# SHALightSwitch.net
KiCad netlist of a schematic drawn in EAGLE
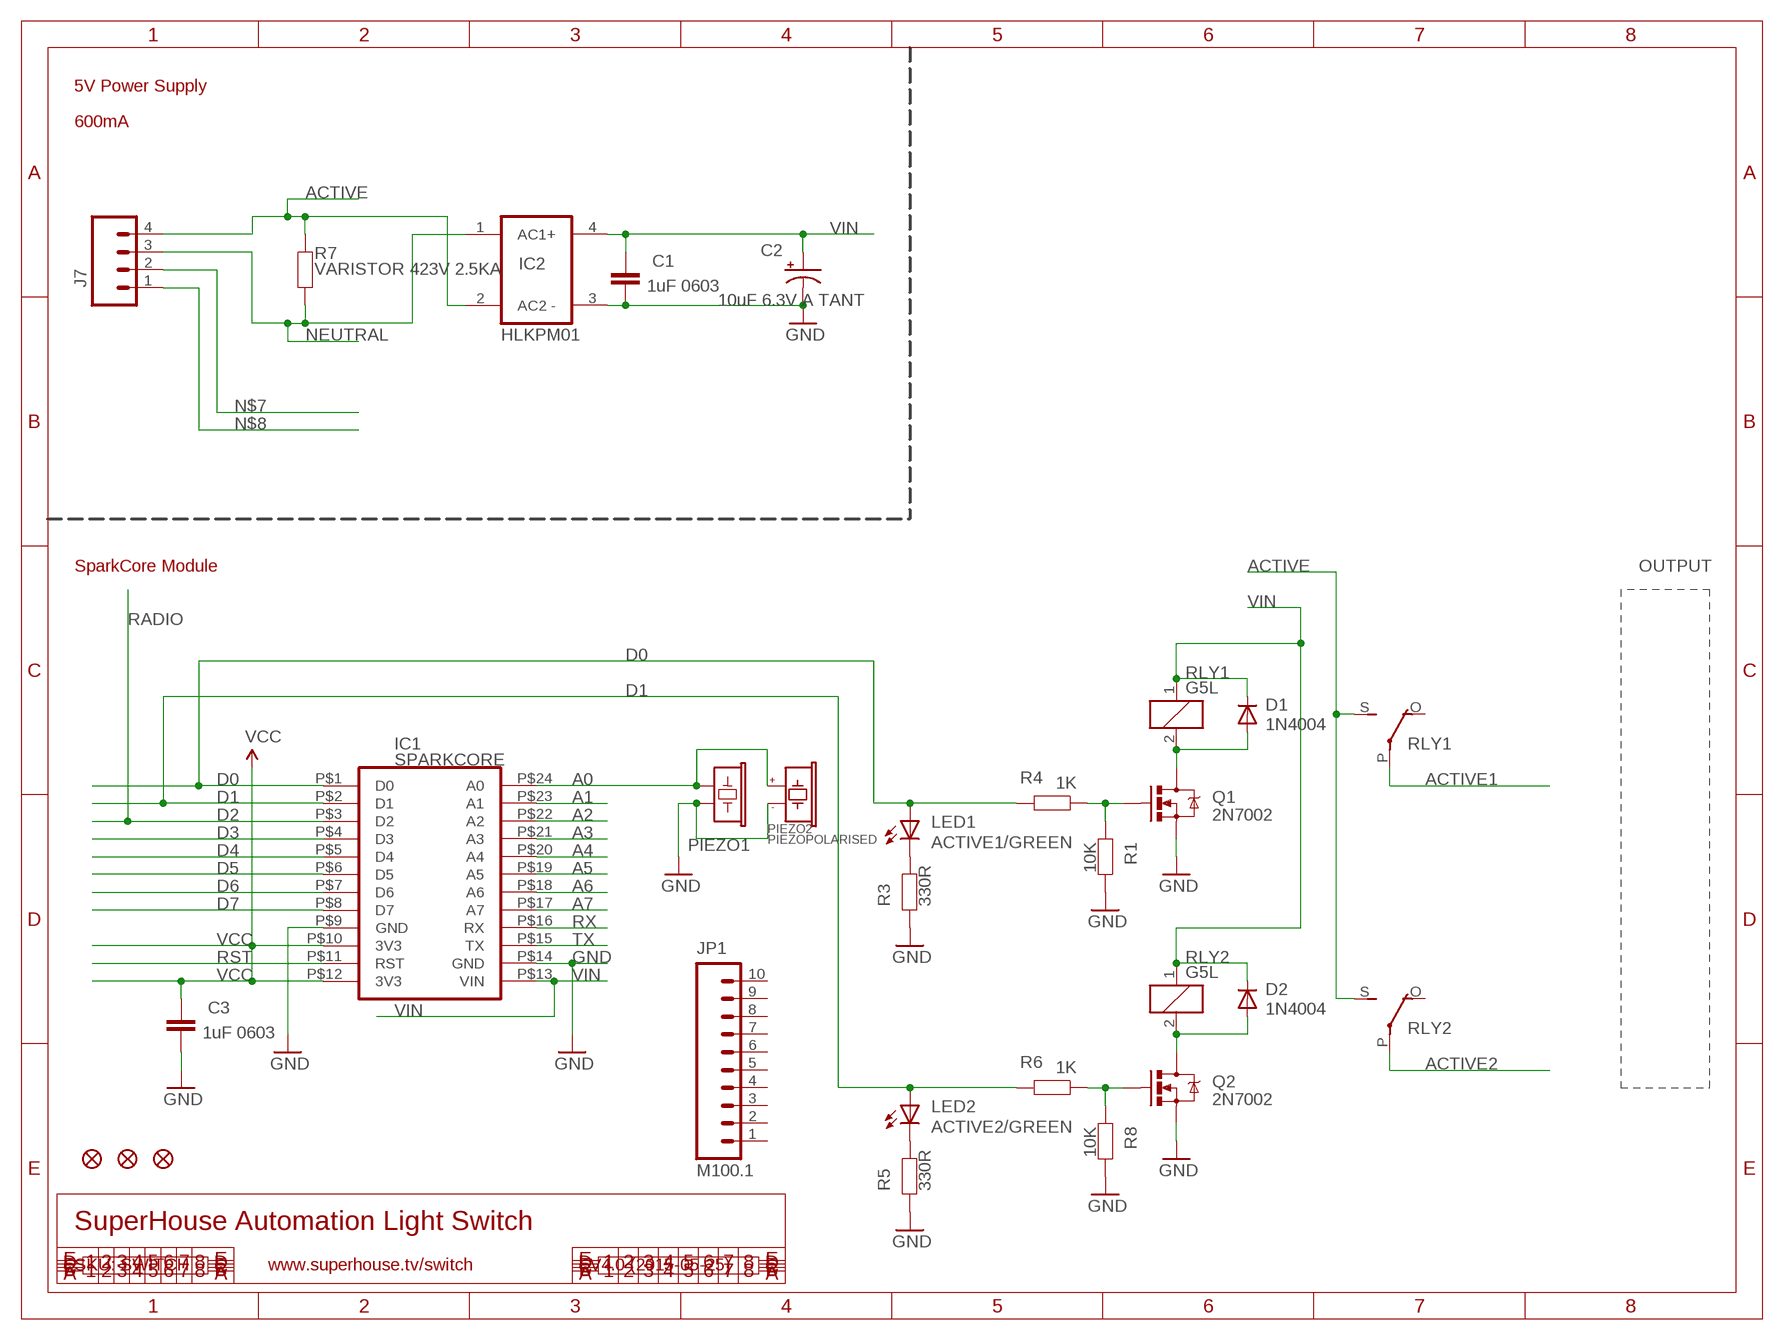
[diagram p0: schematic, sheet 1]

(export (version "E")
  (design (tool "Eeschema 10.0.6"))
  (components
    (comp (ref "C1")
      (value "1uF 0603")
      (footprint "eagle-import:0603@1")
      (libsource (lib "eagle-import") (part "CAP0603"))
    )
    (comp (ref "C2")
      (value "10uF 6.3V A TANT")
      (footprint "eagle-import:EIA3216")
      (libsource (lib "eagle-import") (part "CAP_POL1206"))
    )
    (comp (ref "C3")
      (value "1uF 0603")
      (footprint "eagle-import:0603@1")
      (libsource (lib "eagle-import") (part "CAP0603"))
    )
    (comp (ref "D1")
      (value "1N4004")
      (footprint "eagle-import:SMB-DIODE")
      (libsource (lib "eagle-import") (part "DIODESMB"))
    )
    (comp (ref "D2")
      (value "1N4004")
      (footprint "eagle-import:SMB-DIODE")
      (libsource (lib "eagle-import") (part "DIODESMB"))
    )
    (comp (ref "FID1")
      (value "FIDUCIAL1X2.5")
      (footprint "eagle-import:FIDUCIAL-1X2.5")
      (libsource (lib "eagle-import") (part "FIDUCIAL1X2.5"))
    )
    (comp (ref "FID2")
      (value "FIDUCIAL1X2.5")
      (footprint "eagle-import:FIDUCIAL-1X2.5")
      (libsource (lib "eagle-import") (part "FIDUCIAL1X2.5"))
    )
    (comp (ref "FID3")
      (value "FIDUCIAL1X2.5")
      (footprint "eagle-import:FIDUCIAL-1X2.5")
      (libsource (lib "eagle-import") (part "FIDUCIAL1X2.5"))
    )
    (comp (ref "IC1")
      (value "SPARKCORE")
      (footprint "eagle-import:SPARKCORE")
      (libsource (lib "eagle-import") (part "SPARKCORE"))
    )
    (comp (ref "IC2")
      (value "HLKPM01")
      (footprint "eagle-import:HLKPM01")
      (libsource (lib "eagle-import") (part "HLKPM01"))
    )
    (comp (ref "J7")
      (value "M04SCREW")
      (footprint "eagle-import:SCREWTERMINAL-3.5MM-4")
      (libsource (lib "eagle-import") (part "M04SCREW"))
    )
    (comp (ref "JP1")
      (value "M100.1")
      (footprint "eagle-import:1X10")
      (libsource (lib "eagle-import") (part "M100.1"))
    )
    (comp (ref "LED1")
      (value "ACTIVE1/GREEN")
      (footprint "eagle-import:LED-0603")
      (libsource (lib "eagle-import") (part "LED0603"))
    )
    (comp (ref "LED2")
      (value "ACTIVE2/GREEN")
      (footprint "eagle-import:LED-0603")
      (libsource (lib "eagle-import") (part "LED0603"))
    )
    (comp (ref "PIEZO1")
      (value "BUZZERSMD12X12")
      (footprint "eagle-import:BUZZER-12X12-SMT")
      (libsource (lib "eagle-import") (part "BUZZERSMD12X12"))
    )
    (comp (ref "PIEZO2")
      (value "PIEZOPOLARISED")
      (footprint "eagle-import:PIEZO12MMWIDEPOLARISED")
      (libsource (lib "eagle-import") (part "PIEZOPOLARISED"))
    )
    (comp (ref "Q1")
      (value "2N7002")
      (footprint "eagle-import:SOT23-3")
      (libsource (lib "eagle-import") (part "MOSFET-NCHANNELSMD"))
    )
    (comp (ref "Q2")
      (value "2N7002")
      (footprint "eagle-import:SOT23-3")
      (libsource (lib "eagle-import") (part "MOSFET-NCHANNELSMD"))
    )
    (comp (ref "R1")
      (value "10K")
      (footprint "eagle-import:0603")
      (libsource (lib "eagle-import") (part "RESISTOR0603"))
    )
    (comp (ref "R3")
      (value "330R")
      (footprint "eagle-import:0603")
      (libsource (lib "eagle-import") (part "RESISTOR0603"))
    )
    (comp (ref "R4")
      (value "1K")
      (footprint "eagle-import:0603")
      (libsource (lib "eagle-import") (part "RESISTOR0603"))
    )
    (comp (ref "R5")
      (value "330R")
      (footprint "eagle-import:0603")
      (libsource (lib "eagle-import") (part "RESISTOR0603"))
    )
    (comp (ref "R6")
      (value "1K")
      (footprint "eagle-import:0603")
      (libsource (lib "eagle-import") (part "RESISTOR0603"))
    )
    (comp (ref "R7")
      (value "VARISTOR 423V 2.5KA")
      (footprint "eagle-import:AXIAL-0.3")
      (libsource (lib "eagle-import") (part "freetronics-master-v1.1_RESISTORPTH1"))
    )
    (comp (ref "R8")
      (value "10K")
      (footprint "eagle-import:0603")
      (libsource (lib "eagle-import") (part "RESISTOR0603"))
    )
    (comp (ref "RLY1")
      (value "G5L")
      (footprint "eagle-import:G5LE")
      (libsource (lib "eagle-import") (part "G5L"))
    )
    (comp (ref "RLY2")
      (value "G5L")
      (footprint "eagle-import:G5LE")
      (libsource (lib "eagle-import") (part "G5L"))
    )
  )
  (nets
    (net (code "1") (name "/A0") (class "Default")
      (node (ref "IC1") (pin "P$24") (pinfunction "A0_P$24") (pintype "bidirectional"))
      (node (ref "PIEZO1") (pin "1") (pinfunction "1_1") (pintype "passive"))
      (node (ref "PIEZO2") (pin "1") (pinfunction "+_1") (pintype "bidirectional"))
    )
    (net (code "2") (name "/A1") (class "Default")
      (node (ref "IC1") (pin "P$23") (pinfunction "A1_P$23") (pintype "bidirectional"))
    )
    (net (code "3") (name "/A2") (class "Default")
      (node (ref "IC1") (pin "P$22") (pinfunction "A2_P$22") (pintype "bidirectional"))
    )
    (net (code "4") (name "/A3") (class "Default")
      (node (ref "IC1") (pin "P$21") (pinfunction "A3_P$21") (pintype "bidirectional"))
    )
    (net (code "5") (name "/A4") (class "Default")
      (node (ref "IC1") (pin "P$20") (pinfunction "A4_P$20") (pintype "bidirectional"))
    )
    (net (code "6") (name "/A5") (class "Default")
      (node (ref "IC1") (pin "P$19") (pinfunction "A5_P$19") (pintype "bidirectional"))
    )
    (net (code "7") (name "/A6") (class "Default")
      (node (ref "IC1") (pin "P$18") (pinfunction "A6_P$18") (pintype "bidirectional"))
    )
    (net (code "8") (name "/A7") (class "Default")
      (node (ref "IC1") (pin "P$17") (pinfunction "A7_P$17") (pintype "bidirectional"))
    )
    (net (code "9") (name "/ACTIVE") (class "Default")
      (node (ref "IC2") (pin "2") (pinfunction "AC2_2") (pintype "bidirectional"))
      (node (ref "J7") (pin "4") (pinfunction "4_4") (pintype "passive"))
      (node (ref "R7") (pin "P$2") (pinfunction "2_P$2") (pintype "passive"))
      (node (ref "RLY1") (pin "S") (pinfunction "S_S") (pintype "passive"))
      (node (ref "RLY2") (pin "S") (pinfunction "S_S") (pintype "passive"))
    )
    (net (code "10") (name "/ACTIVE1") (class "Default")
      (node (ref "RLY1") (pin "P") (pinfunction "P_P") (pintype "passive"))
    )
    (net (code "11") (name "/ACTIVE2") (class "Default")
      (node (ref "RLY2") (pin "P") (pinfunction "P_P") (pintype "passive"))
    )
    (net (code "12") (name "/D0") (class "Default")
      (node (ref "IC1") (pin "P$1") (pinfunction "D0_P$1") (pintype "bidirectional"))
      (node (ref "LED1") (pin "A") (pinfunction "A_A") (pintype "passive"))
      (node (ref "R4") (pin "2") (pinfunction "2_2") (pintype "passive"))
    )
    (net (code "13") (name "/D1") (class "Default")
      (node (ref "IC1") (pin "P$2") (pinfunction "D1_P$2") (pintype "bidirectional"))
      (node (ref "LED2") (pin "A") (pinfunction "A_A") (pintype "passive"))
      (node (ref "R6") (pin "2") (pinfunction "2_2") (pintype "passive"))
    )
    (net (code "14") (name "/D2") (class "Default")
      (node (ref "IC1") (pin "P$3") (pinfunction "D2_P$3") (pintype "bidirectional"))
    )
    (net (code "15") (name "/D3") (class "Default")
      (node (ref "IC1") (pin "P$4") (pinfunction "D3_P$4") (pintype "bidirectional"))
    )
    (net (code "16") (name "/D4") (class "Default")
      (node (ref "IC1") (pin "P$5") (pinfunction "D4_P$5") (pintype "bidirectional"))
    )
    (net (code "17") (name "/D5") (class "Default")
      (node (ref "IC1") (pin "P$6") (pinfunction "D5_P$6") (pintype "bidirectional"))
    )
    (net (code "18") (name "/D6") (class "Default")
      (node (ref "IC1") (pin "P$7") (pinfunction "D6_P$7") (pintype "bidirectional"))
    )
    (net (code "19") (name "/D7") (class "Default")
      (node (ref "IC1") (pin "P$8") (pinfunction "D7_P$8") (pintype "bidirectional"))
    )
    (net (code "20") (name "/N$7") (class "Default")
      (node (ref "J7") (pin "2") (pinfunction "2_2") (pintype "passive"))
    )
    (net (code "21") (name "/N$8") (class "Default")
      (node (ref "J7") (pin "1") (pinfunction "1_1") (pintype "passive"))
    )
    (net (code "22") (name "/NEUTRAL") (class "Default")
      (node (ref "IC2") (pin "1") (pinfunction "AC1_1") (pintype "bidirectional"))
      (node (ref "J7") (pin "3") (pinfunction "3_3") (pintype "passive"))
      (node (ref "R7") (pin "P$1") (pinfunction "1_P$1") (pintype "passive"))
    )
    (net (code "23") (name "/RST") (class "Default")
      (node (ref "IC1") (pin "P$11") (pinfunction "RST_P$11") (pintype "bidirectional"))
    )
    (net (code "24") (name "/RX") (class "Default")
      (node (ref "IC1") (pin "P$16") (pinfunction "RX_P$16") (pintype "bidirectional"))
    )
    (net (code "25") (name "/TX") (class "Default")
      (node (ref "IC1") (pin "P$15") (pinfunction "TX_P$15") (pintype "bidirectional"))
    )
    (net (code "26") (name "/VIN") (class "Default")
      (node (ref "C1") (pin "1") (pinfunction "1_1") (pintype "passive"))
      (node (ref "C2") (pin "A") (pinfunction "+_A") (pintype "passive"))
      (node (ref "D1") (pin "C") (pinfunction "C_C") (pintype "passive"))
      (node (ref "D2") (pin "C") (pinfunction "C_C") (pintype "passive"))
      (node (ref "IC1") (pin "P$13") (pinfunction "VIN_P$13") (pintype "bidirectional"))
      (node (ref "IC2") (pin "4") (pinfunction "+_4") (pintype "bidirectional"))
      (node (ref "RLY1") (pin "1") (pinfunction "1_1") (pintype "passive"))
      (node (ref "RLY2") (pin "1") (pinfunction "1_1") (pintype "passive"))
    )
    (net (code "27") (name "GND") (class "Default")
      (node (ref "C1") (pin "2") (pinfunction "2_2") (pintype "passive"))
      (node (ref "C2") (pin "C") (pinfunction "-_C") (pintype "passive"))
      (node (ref "C3") (pin "2") (pinfunction "2_2") (pintype "passive"))
      (node (ref "IC1") (pin "P$14") (pinfunction "GND_P$14") (pintype "bidirectional"))
      (node (ref "IC1") (pin "P$9") (pinfunction "GND_P$9") (pintype "bidirectional"))
      (node (ref "IC2") (pin "3") (pinfunction "-_3") (pintype "bidirectional"))
      (node (ref "PIEZO1") (pin "2") (pinfunction "2_2") (pintype "passive"))
      (node (ref "PIEZO2") (pin "2") (pinfunction "-_2") (pintype "bidirectional"))
      (node (ref "Q1") (pin "2") (pinfunction "S_2") (pintype "passive"))
      (node (ref "Q2") (pin "2") (pinfunction "S_2") (pintype "passive"))
      (node (ref "R1") (pin "2") (pinfunction "2_2") (pintype "passive"))
      (node (ref "R3") (pin "1") (pinfunction "1_1") (pintype "passive"))
      (node (ref "R5") (pin "1") (pinfunction "1_1") (pintype "passive"))
      (node (ref "R8") (pin "2") (pinfunction "2_2") (pintype "passive"))
    )
    (net (code "28") (name "Net-(LED1-PadC)") (class "Default")
      (node (ref "LED1") (pin "C") (pinfunction "C_C") (pintype "passive"))
      (node (ref "R3") (pin "2") (pinfunction "2_2") (pintype "passive"))
    )
    (net (code "29") (name "Net-(LED2-PadC)") (class "Default")
      (node (ref "LED2") (pin "C") (pinfunction "C_C") (pintype "passive"))
      (node (ref "R5") (pin "2") (pinfunction "2_2") (pintype "passive"))
    )
    (net (code "30") (name "Net-(Q1-D)") (class "Default")
      (node (ref "D1") (pin "A") (pinfunction "A_A") (pintype "passive"))
      (node (ref "Q1") (pin "3") (pinfunction "D_3") (pintype "passive"))
      (node (ref "RLY1") (pin "2") (pinfunction "2_2") (pintype "passive"))
    )
    (net (code "31") (name "Net-(Q1-G)") (class "Default")
      (node (ref "Q1") (pin "1") (pinfunction "G_1") (pintype "passive"))
      (node (ref "R1") (pin "1") (pinfunction "1_1") (pintype "passive"))
      (node (ref "R4") (pin "1") (pinfunction "1_1") (pintype "passive"))
    )
    (net (code "32") (name "Net-(Q2-D)") (class "Default")
      (node (ref "D2") (pin "A") (pinfunction "A_A") (pintype "passive"))
      (node (ref "Q2") (pin "3") (pinfunction "D_3") (pintype "passive"))
      (node (ref "RLY2") (pin "2") (pinfunction "2_2") (pintype "passive"))
    )
    (net (code "33") (name "Net-(Q2-G)") (class "Default")
      (node (ref "Q2") (pin "1") (pinfunction "G_1") (pintype "passive"))
      (node (ref "R6") (pin "1") (pinfunction "1_1") (pintype "passive"))
      (node (ref "R8") (pin "1") (pinfunction "1_1") (pintype "passive"))
    )
    (net (code "34") (name "VCC") (class "Default")
      (node (ref "C3") (pin "1") (pinfunction "1_1") (pintype "passive"))
      (node (ref "IC1") (pin "P$10") (pinfunction "3V3_P$10") (pintype "bidirectional"))
      (node (ref "IC1") (pin "P$12") (pinfunction "3V3_P$12") (pintype "bidirectional"))
    )
    (net (code "35") (name "unconnected-(JP1-Pad1)") (class "Default")
      (node (ref "JP1") (pin "1") (pinfunction "1_1") (pintype "passive"))
    )
    (net (code "36") (name "unconnected-(JP1-Pad2)") (class "Default")
      (node (ref "JP1") (pin "2") (pinfunction "2_2") (pintype "passive"))
    )
    (net (code "37") (name "unconnected-(JP1-Pad3)") (class "Default")
      (node (ref "JP1") (pin "3") (pinfunction "3_3") (pintype "passive"))
    )
    (net (code "38") (name "unconnected-(JP1-Pad4)") (class "Default")
      (node (ref "JP1") (pin "4") (pinfunction "4_4") (pintype "passive"))
    )
    (net (code "39") (name "unconnected-(JP1-Pad5)") (class "Default")
      (node (ref "JP1") (pin "5") (pinfunction "5_5") (pintype "passive"))
    )
    (net (code "40") (name "unconnected-(JP1-Pad6)") (class "Default")
      (node (ref "JP1") (pin "6") (pinfunction "6_6") (pintype "passive"))
    )
    (net (code "41") (name "unconnected-(JP1-Pad7)") (class "Default")
      (node (ref "JP1") (pin "7") (pinfunction "7_7") (pintype "passive"))
    )
    (net (code "42") (name "unconnected-(JP1-Pad8)") (class "Default")
      (node (ref "JP1") (pin "8") (pinfunction "8_8") (pintype "passive"))
    )
    (net (code "43") (name "unconnected-(JP1-Pad9)") (class "Default")
      (node (ref "JP1") (pin "9") (pinfunction "9_9") (pintype "passive"))
    )
    (net (code "44") (name "unconnected-(JP1-Pad10)") (class "Default")
      (node (ref "JP1") (pin "10") (pinfunction "10_10") (pintype "passive"))
    )
    (net (code "45") (name "unconnected-(RLY1-PadO)") (class "Default")
      (node (ref "RLY1") (pin "O") (pinfunction "O_O") (pintype "passive"))
    )
    (net (code "46") (name "unconnected-(RLY2-PadO)") (class "Default")
      (node (ref "RLY2") (pin "O") (pinfunction "O_O") (pintype "passive"))
    )
  )
)
